# Any_Thing_Schematic.net
KiCad netlist of a schematic drawn in Altium Designer
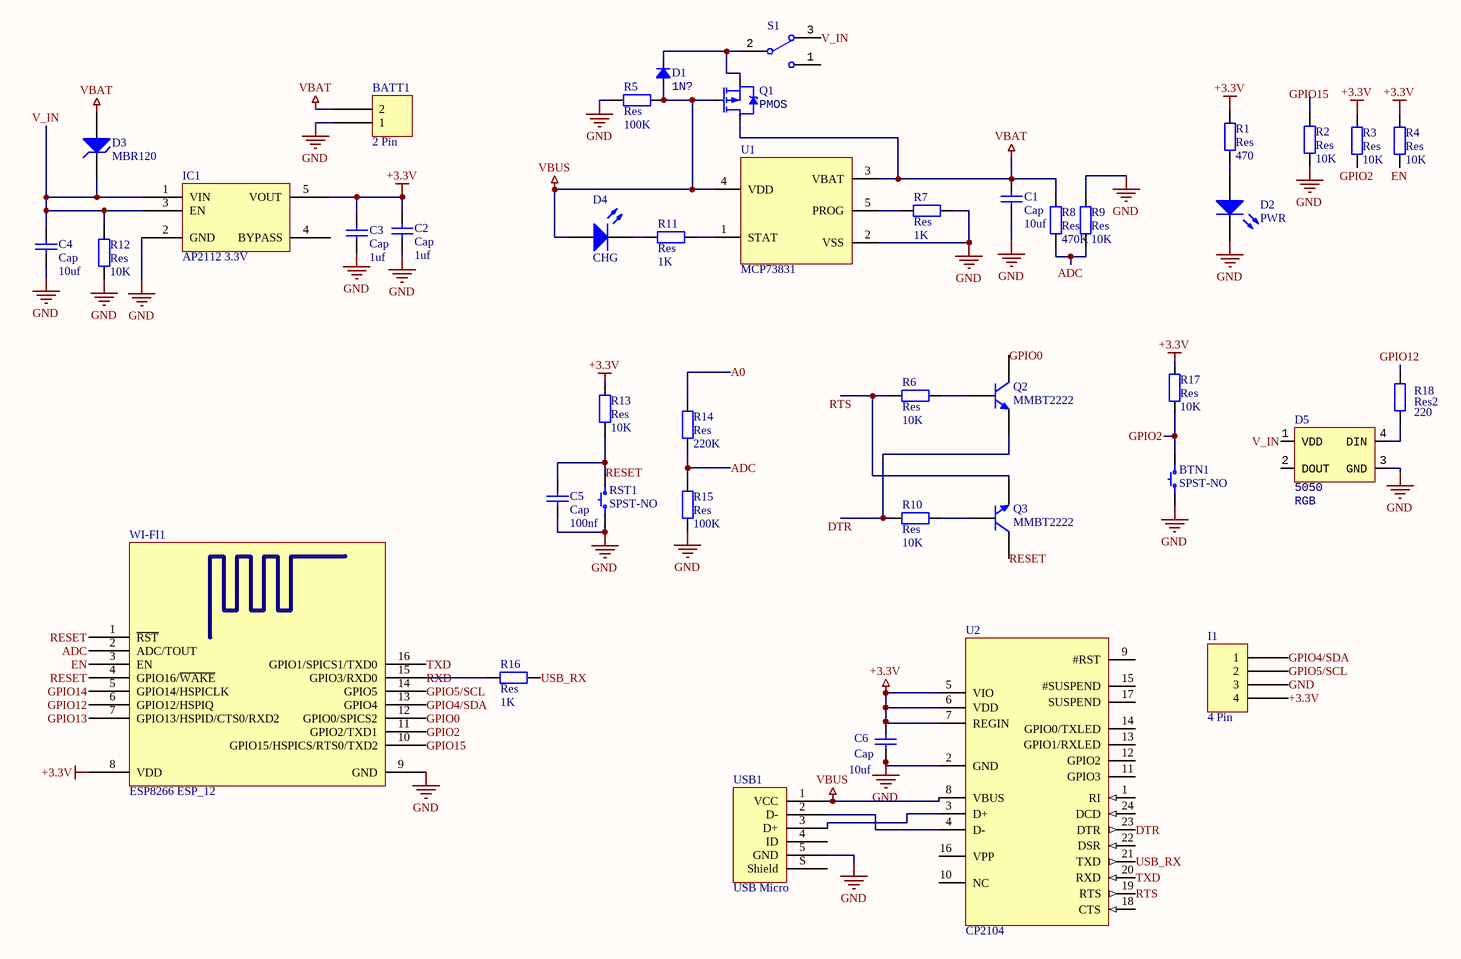
[diagram p0: Any_Thing_Schematic.SchDoc]

(export (version "E")
  (design (tool "Eeschema 10.0.6"))
  (components
    (comp (ref "BATT1")
      (value "2 Pin")
      (footprint "JST B2B-PH-K")
      (libsource (lib "Connectors") (part "2 Pin"))
    )
    (comp (ref "BTN1")
      (value "SPST-NO")
      (footprint "BUT: 12x12")
      (libsource (lib "Button") (part "NKK AB11AH-HA"))
    )
    (comp (ref "C1")
      (value "Cap")
      (footprint "CAP 0805/2012")
      (description "Capacitor")
      (fields (field (name "ALTIUM_VALUE") "10uf") (field (name "PUBLISHER") "Altium Limited"))
      (libsource (lib "Miscellaneous Devices") (part "Cap"))
    )
    (comp (ref "C2")
      (value "Cap")
      (footprint "CAP 0805/2012")
      (description "Capacitor")
      (fields (field (name "ALTIUM_VALUE") "1uf") (field (name "PUBLISHER") "Altium Limited"))
      (libsource (lib "Miscellaneous Devices") (part "Cap"))
    )
    (comp (ref "C3")
      (value "Cap")
      (footprint "CAP 0805/2012")
      (description "Capacitor")
      (fields (field (name "ALTIUM_VALUE") "1uf") (field (name "PUBLISHER") "Altium Limited"))
      (libsource (lib "Miscellaneous Devices") (part "Cap"))
    )
    (comp (ref "C4")
      (value "Cap")
      (footprint "CAP 0805/2012")
      (description "Capacitor")
      (fields (field (name "ALTIUM_VALUE") "10uf") (field (name "PUBLISHER") "Altium Limited"))
      (libsource (lib "Miscellaneous Devices") (part "Cap"))
    )
    (comp (ref "C5")
      (value "Cap")
      (footprint "CAP 0805/2012")
      (description "Capacitor")
      (fields (field (name "ALTIUM_VALUE") "100nf") (field (name "PUBLISHER") "Altium Limited"))
      (libsource (lib "Miscellaneous Devices") (part "Cap"))
    )
    (comp (ref "C6")
      (value "Cap")
      (footprint "CAP 0805/2012")
      (description "Capacitor")
      (fields (field (name "ALTIUM_VALUE") "10uf") (field (name "PUBLISHER") "Altium Limited"))
      (libsource (lib "Miscellaneous Devices") (part "Cap"))
    )
    (comp (ref "D1")
      (value "1N?")
      (footprint "SOD-123")
      (description "Diode")
      (libsource (lib "SCH_Active") (part "Diode_SOD123"))
    )
    (comp (ref "D2")
      (value "PWR")
      (footprint "SMD: LED 0805/2012 RED")
      (description "Typical INFRARED GaAs LED")
      (fields (field (name "PUBLISHER") "Altium Limited"))
      (libsource (lib "Miscellaneous Devices") (part "LED0"))
    )
    (comp (ref "D3")
      (value "MBR120")
      (footprint "SOD-123")
      (description "Zener Diode")
      (fields (field (name "PUBLISHER") "Altium Limited"))
      (libsource (lib "Miscellaneous Devices") (part "D Zener"))
    )
    (comp (ref "D4")
      (value "CHG")
      (footprint "SMD: LED 0805/2012 GREEN")
      (description "Typical INFRARED GaAs LED")
      (fields (field (name "PUBLISHER") "Altium Limited"))
      (libsource (lib "Miscellaneous Devices") (part "LED0"))
    )
    (comp (ref "D5")
      (value "RGB")
      (footprint "SMD_LED_5050_WS2812B")
      (description "LED")
      (fields (field (name "TYPE") "5050"))
      (libsource (lib "SCH_Active") (part "LED_5050_WS2812B"))
    )
    (comp (ref "I1") (value "4 Pin") (libsource (lib "Connectors") (part "4 Pin")))
    (comp (ref "IC1")
      (value "AP2112 3.3V")
      (footprint "TI SOT-23-5 DBV")
      (description "Micropower 150mA Low-Noise Ultra Low-Dropout CMOS Voltage Regulator")
      (libsource (lib "Voltage Regulators Linear") (part "TI LP3985"))
    )
    (comp (ref "Q1")
      (value "PMOS")
      (footprint "INFINEON SOT-23-3")
      (description "MOSFET")
      (libsource (lib "SCH_Active") (part "MOSFET_P_TO252"))
    )
    (comp (ref "Q2")
      (value "MMBT2222")
      (footprint "DIODES SOT-23-3")
      (description "NPN Bipolar Transistor")
      (fields (field (name "PUBLISHER") "Altium Limited"))
      (libsource (lib "Miscellaneous Devices") (part "NPN"))
    )
    (comp (ref "Q3")
      (value "MMBT2222")
      (footprint "DIODES SOT-23-3")
      (description "NPN Bipolar Transistor")
      (fields (field (name "PUBLISHER") "Altium Limited"))
      (libsource (lib "Miscellaneous Devices") (part "NPN"))
    )
    (comp (ref "R1")
      (value "Res")
      (footprint "RES 0805/2012")
      (description "Resistor")
      (fields (field (name "ALTIUM_VALUE") "470") (field (name "PUBLISHER") "Altium Limited"))
      (libsource (lib "") (part "Res2_1"))
    )
    (comp (ref "R2")
      (value "Res")
      (footprint "RES 0805/2012")
      (description "Resistor")
      (fields (field (name "ALTIUM_VALUE") "10K") (field (name "PUBLISHER") "Altium Limited"))
      (libsource (lib "") (part "Res2_2"))
    )
    (comp (ref "R3")
      (value "Res")
      (footprint "RES 0805/2012")
      (description "Resistor")
      (fields (field (name "ALTIUM_VALUE") "10K") (field (name "PUBLISHER") "Altium Limited"))
      (libsource (lib "") (part "Res2_2"))
    )
    (comp (ref "R4")
      (value "Res")
      (footprint "RES 0805/2012")
      (description "Resistor")
      (fields (field (name "ALTIUM_VALUE") "10K") (field (name "PUBLISHER") "Altium Limited"))
      (libsource (lib "") (part "Res2_2"))
    )
    (comp (ref "R5")
      (value "Res")
      (footprint "RES 0805/2012")
      (description "Resistor")
      (fields (field (name "ALTIUM_VALUE") "100K") (field (name "PUBLISHER") "Altium Limited"))
      (libsource (lib "") (part "Res2_1"))
    )
    (comp (ref "R6")
      (value "Res")
      (footprint "RES 0805/2012")
      (description "Resistor")
      (fields (field (name "ALTIUM_VALUE") "10K") (field (name "PUBLISHER") "Altium Limited"))
      (libsource (lib "") (part "Res2_1"))
    )
    (comp (ref "R7")
      (value "Res")
      (footprint "RES 0805/2012")
      (description "Resistor")
      (fields (field (name "ALTIUM_VALUE") "1K") (field (name "PUBLISHER") "Altium Limited"))
      (libsource (lib "") (part "Res2_1"))
    )
    (comp (ref "R8")
      (value "Res")
      (footprint "RES 0805/2012")
      (description "Resistor")
      (fields (field (name "ALTIUM_VALUE") "470K") (field (name "PUBLISHER") "Altium Limited"))
      (libsource (lib "") (part "Res2_1"))
    )
    (comp (ref "R9")
      (value "Res")
      (footprint "RES 0805/2012")
      (description "Resistor")
      (fields (field (name "ALTIUM_VALUE") "10K") (field (name "PUBLISHER") "Altium Limited"))
      (libsource (lib "") (part "Res2_2"))
    )
    (comp (ref "R10")
      (value "Res")
      (footprint "RES 0805/2012")
      (description "Resistor")
      (fields (field (name "ALTIUM_VALUE") "10K") (field (name "PUBLISHER") "Altium Limited"))
      (libsource (lib "") (part "Res2_1"))
    )
    (comp (ref "R11")
      (value "Res")
      (footprint "RES 0805/2012")
      (description "Resistor")
      (fields (field (name "ALTIUM_VALUE") "1K") (field (name "PUBLISHER") "Altium Limited"))
      (libsource (lib "") (part "Res2_1"))
    )
    (comp (ref "R12")
      (value "Res")
      (footprint "RES 0805/2012")
      (description "Resistor")
      (fields (field (name "ALTIUM_VALUE") "10K") (field (name "PUBLISHER") "Altium Limited"))
      (libsource (lib "Miscellaneous Devices") (part "Res2"))
    )
    (comp (ref "R13")
      (value "Res")
      (footprint "RES 0805/2012")
      (description "Resistor")
      (fields (field (name "ALTIUM_VALUE") "10K") (field (name "PUBLISHER") "Altium Limited"))
      (libsource (lib "Miscellaneous Devices") (part "Res2"))
    )
    (comp (ref "R14")
      (value "Res")
      (footprint "RES 0805/2012")
      (description "Resistor")
      (fields (field (name "ALTIUM_VALUE") "220K") (field (name "PUBLISHER") "Altium Limited"))
      (libsource (lib "") (part "Res2_2"))
    )
    (comp (ref "R15")
      (value "Res")
      (footprint "RES 0805/2012")
      (description "Resistor")
      (fields (field (name "ALTIUM_VALUE") "100K") (field (name "PUBLISHER") "Altium Limited"))
      (libsource (lib "") (part "Res2_2"))
    )
    (comp (ref "R16")
      (value "Res")
      (footprint "RES 0805/2012")
      (description "Resistor")
      (fields (field (name "ALTIUM_VALUE") "1K") (field (name "PUBLISHER") "Altium Limited"))
      (libsource (lib "") (part "Res2_1"))
    )
    (comp (ref "R17")
      (value "Res")
      (footprint "RES 0805/2012")
      (description "Resistor")
      (fields (field (name "ALTIUM_VALUE") "10K") (field (name "PUBLISHER") "Altium Limited"))
      (libsource (lib "Miscellaneous Devices") (part "Res2"))
    )
    (comp (ref "R18")
      (value "Res2")
      (footprint "RES 0805/2012")
      (description "Resistor")
      (fields (field (name "ALTIUM_VALUE") "220") (field (name "PUBLISHER") "Altium Limited"))
      (libsource (lib "Miscellaneous Devices") (part "Res2"))
    )
    (comp (ref "RST1")
      (value "SPST-NO")
      (footprint "ButtonTACT_4P_3x4x2_180")
      (libsource (lib "Button") (part "NKK AB11AH-HA"))
    )
    (comp (ref "S1")
      (value "SPDT 3P")
      (footprint "Switch: SPDT_4.3X8.6_D90")
      (description "Switch")
      (libsource (lib "SCH_Switch") (part "SwitchSPDT_2.8x6.6_90"))
    )
    (comp (ref "U1")
      (value "MCP73831")
      (footprint "TI SOT-23-5 DBV")
      (libsource (lib "basit") (part "MCP73831"))
    )
    (comp (ref "U2") (value "CP2104") (footprint "24-QFN") (libsource (lib "basit") (part "CP2104")))
    (comp (ref "USB1")
      (value "USB Micro")
      (footprint "FCI USB 10118193-0001LF")
      (libsource (lib "Connectors") (part "USB 2.0 Type B Micro"))
    )
    (comp (ref "WI-FI1")
      (value "ESP8266 ESP_12")
      (footprint "ESP8266 ESP_12")
      (description "ESP8266 ESP-12")
      (fields (field (name "PUBLISHER") "Cynetik Group") (field (name "LATESTREVIEWER") "Zion Blue"))
      (libsource (lib "ESP8266") (part "ESP8266 ESP_12"))
    )
  )
  (nets
    (net (code "1") (name "+3.3V") (class "Default")
      (node (ref "C2") (pin "2") (pinfunction "2_2") (pintype "passive"))
      (node (ref "C3") (pin "2") (pinfunction "2_2") (pintype "passive"))
      (node (ref "C6") (pin "2") (pinfunction "2_2") (pintype "passive"))
      (node (ref "I1") (pin "4") (pinfunction "4_4") (pintype "passive"))
      (node (ref "IC1") (pin "5") (pinfunction "VOUT_5") (pintype "passive"))
      (node (ref "R1") (pin "1") (pinfunction "1_1") (pintype "passive"))
      (node (ref "R13") (pin "2") (pinfunction "2_2") (pintype "passive"))
      (node (ref "R17") (pin "2") (pinfunction "2_2") (pintype "passive"))
      (node (ref "R3") (pin "1") (pinfunction "1_1") (pintype "passive"))
      (node (ref "R4") (pin "1") (pinfunction "1_1") (pintype "passive"))
      (node (ref "U2") (pin "5") (pinfunction "VIO_5") (pintype "passive"))
      (node (ref "U2") (pin "6") (pinfunction "VDD_6") (pintype "passive"))
      (node (ref "U2") (pin "7") (pinfunction "REGIN_7") (pintype "passive"))
      (node (ref "WI-FI1") (pin "8") (pinfunction "VDD_8") (pintype "passive"))
    )
    (net (code "2") (name "/A0") (class "Default")
      (node (ref "R14") (pin "1") (pinfunction "1_1") (pintype "passive"))
    )
    (net (code "3") (name "/ADC") (class "Default")
      (node (ref "R14") (pin "2") (pinfunction "2_2") (pintype "passive"))
      (node (ref "R15") (pin "1") (pinfunction "1_1") (pintype "passive"))
      (node (ref "R8") (pin "2") (pinfunction "2_2") (pintype "passive"))
      (node (ref "R9") (pin "2") (pinfunction "2_2") (pintype "passive"))
      (node (ref "WI-FI1") (pin "2") (pinfunction "ADC/TOUT_2") (pintype "passive"))
    )
    (net (code "4") (name "/DTR") (class "Default")
      (node (ref "Q2") (pin "3") (pinfunction "E_3") (pintype "passive"))
      (node (ref "R10") (pin "2") (pinfunction "2_2") (pintype "passive"))
      (node (ref "U2") (pin "23") (pinfunction "DTR_23") (pintype "output"))
    )
    (net (code "5") (name "/EN") (class "Default")
      (node (ref "R4") (pin "2") (pinfunction "2_2") (pintype "passive"))
      (node (ref "WI-FI1") (pin "3") (pinfunction "EN_3") (pintype "passive"))
    )
    (net (code "6") (name "/GPIO0") (class "Default")
      (node (ref "Q2") (pin "1") (pinfunction "C_1") (pintype "passive"))
      (node (ref "WI-FI1") (pin "12") (pinfunction "GPIO0/SPICS2_12") (pintype "passive"))
    )
    (net (code "7") (name "/GPIO2") (class "Default")
      (node (ref "BTN1") (pin "3") (pinfunction "3_3") (pintype "passive"))
      (node (ref "R17") (pin "1") (pinfunction "1_1") (pintype "passive"))
      (node (ref "R3") (pin "2") (pinfunction "2_2") (pintype "passive"))
      (node (ref "WI-FI1") (pin "11") (pinfunction "GPIO2/TXD1_11") (pintype "passive"))
    )
    (net (code "8") (name "/GPIO4{slash}SDA") (class "Default")
      (node (ref "I1") (pin "1") (pinfunction "1_1") (pintype "passive"))
      (node (ref "WI-FI1") (pin "13") (pinfunction "GPIO4_13") (pintype "passive"))
    )
    (net (code "9") (name "/GPIO5{slash}SCL") (class "Default")
      (node (ref "I1") (pin "2") (pinfunction "2_2") (pintype "passive"))
      (node (ref "WI-FI1") (pin "14") (pinfunction "GPIO5_14") (pintype "passive"))
    )
    (net (code "10") (name "/GPIO12") (class "Default")
      (node (ref "R18") (pin "2") (pinfunction "2_2") (pintype "passive"))
      (node (ref "WI-FI1") (pin "6") (pinfunction "GPIO12/HSPIQ_6") (pintype "passive"))
    )
    (net (code "11") (name "/GPIO13") (class "Default")
      (node (ref "WI-FI1") (pin "7") (pinfunction "GPIO13/HSPID/CTS0/RXD2_7") (pintype "passive"))
    )
    (net (code "12") (name "/GPIO14") (class "Default")
      (node (ref "WI-FI1") (pin "5") (pinfunction "GPIO14/HSPICLK_5") (pintype "passive"))
    )
    (net (code "13") (name "/GPIO15") (class "Default")
      (node (ref "R2") (pin "1") (pinfunction "1_1") (pintype "passive"))
      (node (ref "WI-FI1") (pin "10") (pinfunction "GPIO15/HSPICS/RTS0/TXD2_10") (pintype "passive"))
    )
    (net (code "14") (name "/RESET") (class "Default")
      (node (ref "C5") (pin "2") (pinfunction "2_2") (pintype "passive"))
      (node (ref "Q3") (pin "1") (pinfunction "C_1") (pintype "passive"))
      (node (ref "R13") (pin "1") (pinfunction "1_1") (pintype "passive"))
      (node (ref "RST1") (pin "3") (pinfunction "3_3") (pintype "passive"))
      (node (ref "WI-FI1") (pin "1") (pinfunction "~{RST}_1") (pintype "passive"))
      (node (ref "WI-FI1") (pin "4") (pinfunction "GPIO16/~{WAKE}_4") (pintype "passive"))
    )
    (net (code "15") (name "/RTS") (class "Default")
      (node (ref "Q3") (pin "3") (pinfunction "E_3") (pintype "passive"))
      (node (ref "R6") (pin "2") (pinfunction "2_2") (pintype "passive"))
      (node (ref "U2") (pin "19") (pinfunction "RTS_19") (pintype "output"))
    )
    (net (code "16") (name "/RXD") (class "Default")
      (node (ref "R16") (pin "2") (pinfunction "2_2") (pintype "passive"))
      (node (ref "WI-FI1") (pin "15") (pinfunction "GPIO3/RXD0_15") (pintype "passive"))
    )
    (net (code "17") (name "/TXD") (class "Default")
      (node (ref "U2") (pin "20") (pinfunction "RXD_20") (pintype "input"))
      (node (ref "WI-FI1") (pin "16") (pinfunction "GPIO1/SPICS1/TXD0_16") (pintype "passive"))
    )
    (net (code "18") (name "/USB_RX") (class "Default")
      (node (ref "R16") (pin "1") (pinfunction "1_1") (pintype "passive"))
      (node (ref "U2") (pin "21") (pinfunction "TXD_21") (pintype "output"))
    )
    (net (code "19") (name "/V_IN") (class "Default")
      (node (ref "C4") (pin "2") (pinfunction "2_2") (pintype "passive"))
      (node (ref "D3") (pin "2") (pinfunction "K_2") (pintype "passive"))
      (node (ref "D5") (pin "1") (pinfunction "VDD_1") (pintype "passive"))
      (node (ref "IC1") (pin "1") (pinfunction "VIN_1") (pintype "passive"))
      (node (ref "IC1") (pin "3") (pinfunction "EN_3") (pintype "passive"))
      (node (ref "R12") (pin "2") (pinfunction "2_2") (pintype "passive"))
      (node (ref "S1") (pin "3") (pinfunction "3_3") (pintype "passive"))
    )
    (net (code "20") (name "GND") (class "Default")
      (node (ref "BATT1") (pin "1") (pinfunction "1_1") (pintype "passive"))
      (node (ref "BTN1") (pin "1") (pinfunction "1_1") (pintype "passive"))
      (node (ref "C1") (pin "1") (pinfunction "1_1") (pintype "passive"))
      (node (ref "C2") (pin "1") (pinfunction "1_1") (pintype "passive"))
      (node (ref "C3") (pin "1") (pinfunction "1_1") (pintype "passive"))
      (node (ref "C4") (pin "1") (pinfunction "1_1") (pintype "passive"))
      (node (ref "C5") (pin "1") (pinfunction "1_1") (pintype "passive"))
      (node (ref "C6") (pin "1") (pinfunction "1_1") (pintype "passive"))
      (node (ref "D2") (pin "2") (pinfunction "K_2") (pintype "passive"))
      (node (ref "D5") (pin "3") (pinfunction "GND_3") (pintype "passive"))
      (node (ref "I1") (pin "3") (pinfunction "3_3") (pintype "passive"))
      (node (ref "IC1") (pin "2") (pinfunction "GND_2") (pintype "passive"))
      (node (ref "R12") (pin "1") (pinfunction "1_1") (pintype "passive"))
      (node (ref "R15") (pin "2") (pinfunction "2_2") (pintype "passive"))
      (node (ref "R2") (pin "2") (pinfunction "2_2") (pintype "passive"))
      (node (ref "R5") (pin "2") (pinfunction "2_2") (pintype "passive"))
      (node (ref "R7") (pin "1") (pinfunction "1_1") (pintype "passive"))
      (node (ref "R9") (pin "1") (pinfunction "1_1") (pintype "passive"))
      (node (ref "RST1") (pin "1") (pinfunction "1_1") (pintype "passive"))
      (node (ref "U1") (pin "2") (pinfunction "VSS_2") (pintype "passive"))
      (node (ref "U2") (pin "2") (pinfunction "GND_2") (pintype "passive"))
      (node (ref "USB1") (pin "5") (pinfunction "GND_5") (pintype "passive"))
      (node (ref "WI-FI1") (pin "9") (pinfunction "GND_9") (pintype "passive"))
    )
    (net (code "21") (name "Net-(D1-K)") (class "Default")
      (node (ref "D1") (pin "2") (pinfunction "K_2") (pintype "passive"))
      (node (ref "Q1") (pin "3") (pinfunction "S_3") (pintype "passive"))
      (node (ref "S1") (pin "2") (pinfunction "2_2") (pintype "passive"))
    )
    (net (code "22") (name "Net-(D2-A)") (class "Default")
      (node (ref "D2") (pin "1") (pinfunction "A_1") (pintype "passive"))
      (node (ref "R1") (pin "2") (pinfunction "2_2") (pintype "passive"))
    )
    (net (code "23") (name "Net-(D4-K)") (class "Default")
      (node (ref "D4") (pin "2") (pinfunction "K_2") (pintype "passive"))
      (node (ref "R11") (pin "2") (pinfunction "2_2") (pintype "passive"))
    )
    (net (code "24") (name "Net-(D5-DIN)") (class "Default")
      (node (ref "D5") (pin "4") (pinfunction "DIN_4") (pintype "passive"))
      (node (ref "R18") (pin "1") (pinfunction "1_1") (pintype "passive"))
    )
    (net (code "25") (name "Net-(Q2-B)") (class "Default")
      (node (ref "Q2") (pin "2") (pinfunction "B_2") (pintype "passive"))
      (node (ref "R6") (pin "1") (pinfunction "1_1") (pintype "passive"))
    )
    (net (code "26") (name "Net-(Q3-B)") (class "Default")
      (node (ref "Q3") (pin "2") (pinfunction "B_2") (pintype "passive"))
      (node (ref "R10") (pin "1") (pinfunction "1_1") (pintype "passive"))
    )
    (net (code "27") (name "Net-(U1-PROG)") (class "Default")
      (node (ref "R7") (pin "2") (pinfunction "2_2") (pintype "passive"))
      (node (ref "U1") (pin "5") (pinfunction "PROG_5") (pintype "passive"))
    )
    (net (code "28") (name "Net-(U1-STAT)") (class "Default")
      (node (ref "R11") (pin "1") (pinfunction "1_1") (pintype "passive"))
      (node (ref "U1") (pin "1") (pinfunction "STAT_1") (pintype "passive"))
    )
    (net (code "29") (name "Net-(U2-D+)") (class "Default")
      (node (ref "U2") (pin "3") (pinfunction "D+_3") (pintype "passive"))
      (node (ref "USB1") (pin "3") (pinfunction "D+_3") (pintype "passive"))
    )
    (net (code "30") (name "Net-(U2-D-)") (class "Default")
      (node (ref "U2") (pin "4") (pinfunction "D-_4") (pintype "passive"))
      (node (ref "USB1") (pin "2") (pinfunction "D-_2") (pintype "passive"))
    )
    (net (code "31") (name "VBAT") (class "Default")
      (node (ref "BATT1") (pin "2") (pinfunction "2_2") (pintype "passive"))
      (node (ref "C1") (pin "2") (pinfunction "2_2") (pintype "passive"))
      (node (ref "D3") (pin "1") (pinfunction "A_1") (pintype "passive"))
      (node (ref "Q1") (pin "4") (pinfunction "D_4") (pintype "passive"))
      (node (ref "R8") (pin "1") (pinfunction "1_1") (pintype "passive"))
      (node (ref "U1") (pin "3") (pinfunction "VBAT_3") (pintype "passive"))
    )
    (net (code "32") (name "VBUS") (class "Default")
      (node (ref "D1") (pin "1") (pinfunction "A_1") (pintype "passive"))
      (node (ref "D4") (pin "1") (pinfunction "A_1") (pintype "passive"))
      (node (ref "Q1") (pin "1") (pinfunction "G_1") (pintype "passive"))
      (node (ref "R5") (pin "1") (pinfunction "1_1") (pintype "passive"))
      (node (ref "U1") (pin "4") (pinfunction "VDD_4") (pintype "passive"))
      (node (ref "U2") (pin "8") (pinfunction "VBUS_8") (pintype "passive"))
      (node (ref "USB1") (pin "1") (pinfunction "VCC_1") (pintype "passive"))
    )
    (net (code "33") (name "unconnected-(D5-DOUT-Pad2)") (class "Default")
      (node (ref "D5") (pin "2") (pinfunction "DOUT_2") (pintype "passive"))
    )
    (net (code "34") (name "unconnected-(IC1-BYPASS-Pad4)") (class "Default")
      (node (ref "IC1") (pin "4") (pinfunction "BYPASS_4") (pintype "passive"))
    )
    (net (code "35") (name "unconnected-(S1-Pad1)") (class "Default")
      (node (ref "S1") (pin "1") (pinfunction "1_1") (pintype "passive"))
    )
    (net (code "36") (name "unconnected-(U2-#RST-Pad9)") (class "Default")
      (node (ref "U2") (pin "9") (pinfunction "#RST_9") (pintype "passive"))
    )
    (net (code "37") (name "unconnected-(U2-#SUSPEND-Pad15)") (class "Default")
      (node (ref "U2") (pin "15") (pinfunction "#SUSPEND_15") (pintype "passive"))
    )
    (net (code "38") (name "unconnected-(U2-CTS-Pad18)") (class "Default")
      (node (ref "U2") (pin "18") (pinfunction "CTS_18") (pintype "input"))
    )
    (net (code "39") (name "unconnected-(U2-DCD-Pad24)") (class "Default")
      (node (ref "U2") (pin "24") (pinfunction "DCD_24") (pintype "input"))
    )
    (net (code "40") (name "unconnected-(U2-DSR-Pad22)") (class "Default")
      (node (ref "U2") (pin "22") (pinfunction "DSR_22") (pintype "input"))
    )
    (net (code "41") (name "unconnected-(U2-GPIO0{slash}TXLED-Pad14)") (class "Default")
      (node (ref "U2") (pin "14") (pinfunction "GPIO0/TXLED_14") (pintype "passive"))
    )
    (net (code "42") (name "unconnected-(U2-GPIO1{slash}RXLED-Pad13)") (class "Default")
      (node (ref "U2") (pin "13") (pinfunction "GPIO1/RXLED_13") (pintype "passive"))
    )
    (net (code "43") (name "unconnected-(U2-GPIO2-Pad12)") (class "Default")
      (node (ref "U2") (pin "12") (pinfunction "GPIO2_12") (pintype "passive"))
    )
    (net (code "44") (name "unconnected-(U2-GPIO3-Pad11)") (class "Default")
      (node (ref "U2") (pin "11") (pinfunction "GPIO3_11") (pintype "passive"))
    )
    (net (code "45") (name "unconnected-(U2-NC-Pad10)") (class "Default")
      (node (ref "U2") (pin "10") (pinfunction "NC_10") (pintype "passive"))
    )
    (net (code "46") (name "unconnected-(U2-RI-Pad1)") (class "Default")
      (node (ref "U2") (pin "1") (pinfunction "RI_1") (pintype "input"))
    )
    (net (code "47") (name "unconnected-(U2-SUSPEND-Pad17)") (class "Default")
      (node (ref "U2") (pin "17") (pinfunction "SUSPEND_17") (pintype "passive"))
    )
    (net (code "48") (name "unconnected-(U2-VPP-Pad16)") (class "Default")
      (node (ref "U2") (pin "16") (pinfunction "VPP_16") (pintype "passive"))
    )
    (net (code "49") (name "unconnected-(USB1-ID-Pad4)") (class "Default")
      (node (ref "USB1") (pin "4") (pinfunction "ID_4") (pintype "passive"))
    )
    (net (code "50") (name "unconnected-(USB1-Shield-PadS)") (class "Default")
      (node (ref "USB1") (pin "S") (pinfunction "Shield_S") (pintype "passive"))
    )
  )
)
